# qcopter_lib_bb.net
KiCad netlist of a schematic drawn in EAGLE
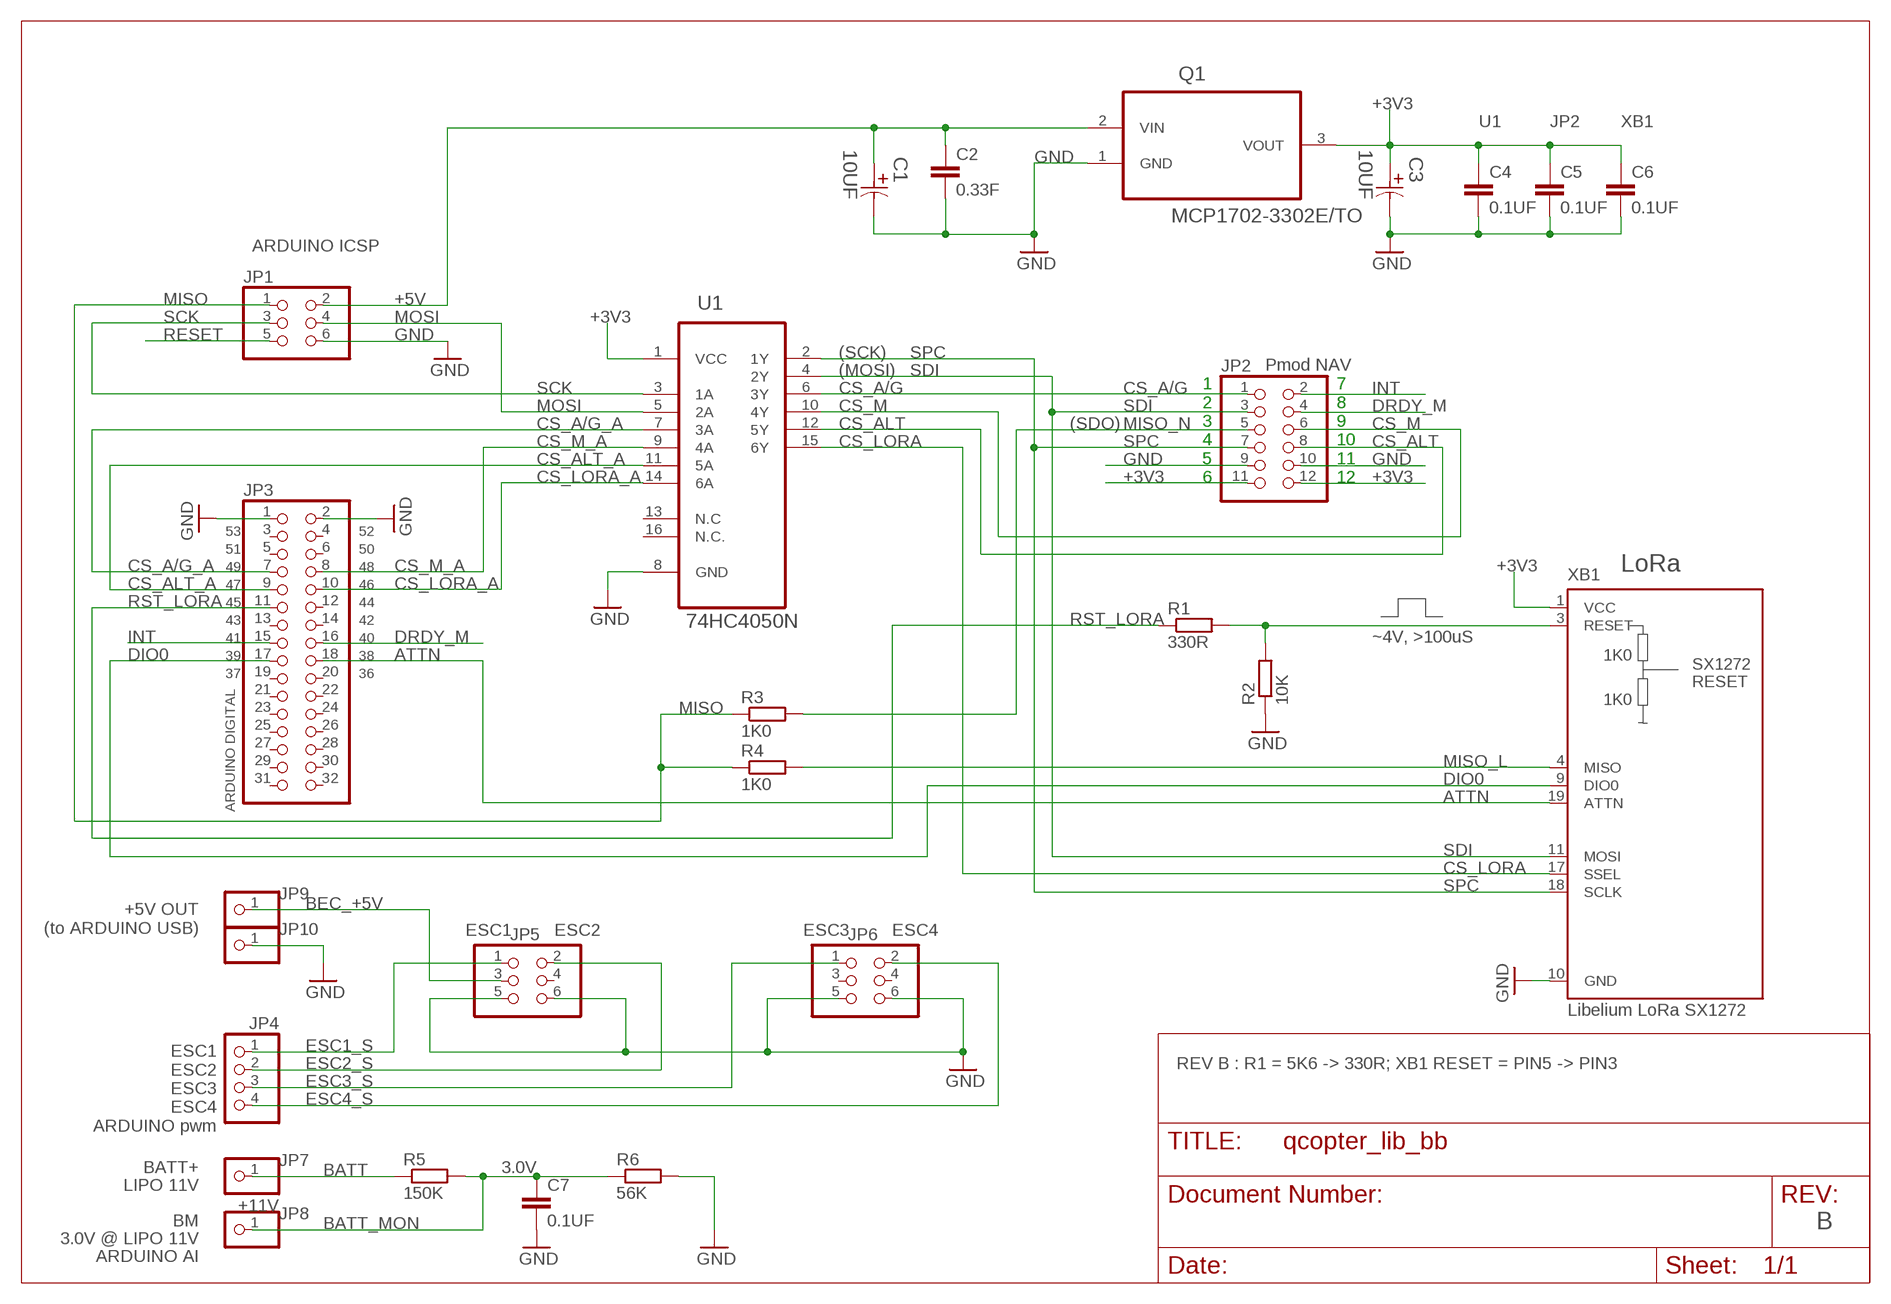
[diagram p0: schematic, sheet 1]

(export (version "E")
  (design (tool "Eeschema 10.0.6"))
  (components
    (comp (ref "C1")
      (value "10UF")
      (footprint "eagle-import:CAPPR200-500X1100")
      (fields (field (name "MPN") "ECA1EHG470") (field (name "TOLERANCE") "±20 %"))
      (libsource (lib "eagle-import") (part "ECA-D5XP21EHG470"))
    )
    (comp (ref "C2")
      (value "0.33F")
      (footprint "eagle-import:C5B2.5")
      (libsource (lib "eagle-import") (part "C5/2.5"))
    )
    (comp (ref "C3")
      (value "10UF")
      (footprint "eagle-import:CAPPR200-500X1100")
      (fields (field (name "MPN") "ECA1EHG470") (field (name "TOLERANCE") "±20 %"))
      (libsource (lib "eagle-import") (part "ECA-D5XP21EHG470"))
    )
    (comp (ref "C4")
      (value "0.1UF")
      (footprint "eagle-import:C5B2.5")
      (libsource (lib "eagle-import") (part "C5/2.5"))
    )
    (comp (ref "C5")
      (value "0.1UF")
      (footprint "eagle-import:C5B2.5")
      (libsource (lib "eagle-import") (part "C5/2.5"))
    )
    (comp (ref "C6")
      (value "0.1UF")
      (footprint "eagle-import:C5B2.5")
      (libsource (lib "eagle-import") (part "C5/2.5"))
    )
    (comp (ref "C7")
      (value "0.1UF")
      (footprint "eagle-import:C5B2.5")
      (libsource (lib "eagle-import") (part "C5/2.5"))
    )
    (comp (ref "JP1")
      (value "PINHD-2X3")
      (footprint "eagle-import:2X03")
      (libsource (lib "eagle-import") (part "PINHD-2X3"))
    )
    (comp (ref "JP2")
      (value "PINHD-2X6/90")
      (footprint "eagle-import:2X06_90")
      (libsource (lib "eagle-import") (part "PINHD-2X6/90"))
    )
    (comp (ref "JP3")
      (value "PINHD-2X16")
      (footprint "eagle-import:2X16")
      (libsource (lib "eagle-import") (part "PINHD-2X16"))
    )
    (comp (ref "JP4")
      (value "PINHD-1X4")
      (footprint "eagle-import:1X04")
      (libsource (lib "eagle-import") (part "PINHD-1X4"))
    )
    (comp (ref "JP5")
      (value "PINHD-2X3")
      (footprint "eagle-import:2X03")
      (libsource (lib "eagle-import") (part "PINHD-2X3"))
    )
    (comp (ref "JP6")
      (value "PINHD-2X3")
      (footprint "eagle-import:2X03")
      (libsource (lib "eagle-import") (part "PINHD-2X3"))
    )
    (comp (ref "JP7")
      (value "+11V")
      (footprint "eagle-import:1X01")
      (libsource (lib "eagle-import") (part "PINHD-1X1"))
    )
    (comp (ref "JP8")
      (value "PINHD-1X1")
      (footprint "eagle-import:1X01")
      (libsource (lib "eagle-import") (part "PINHD-1X1"))
    )
    (comp (ref "JP9")
      (value "PINHD-1X1")
      (footprint "eagle-import:1X01")
      (libsource (lib "eagle-import") (part "PINHD-1X1"))
    )
    (comp (ref "JP10")
      (value "PINHD-1X1")
      (footprint "eagle-import:1X01")
      (libsource (lib "eagle-import") (part "PINHD-1X1"))
    )
    (comp (ref "Q1")
      (value "MCP1702-3302E/TO")
      (footprint "eagle-import:TO127P254X533-3")
      (libsource (lib "eagle-import") (part "MCP1702-3302E/TO"))
    )
    (comp (ref "R1")
      (value "330R")
      (footprint "eagle-import:0207_10")
      (libsource (lib "eagle-import") (part "R-EU_0207/10"))
    )
    (comp (ref "R2")
      (value "10K")
      (footprint "eagle-import:0207_10")
      (libsource (lib "eagle-import") (part "R-EU_0207/10"))
    )
    (comp (ref "R3")
      (value "1K0")
      (footprint "eagle-import:0207_10")
      (libsource (lib "eagle-import") (part "R-EU_0207/10"))
    )
    (comp (ref "R4")
      (value "1K0")
      (footprint "eagle-import:0207_10")
      (libsource (lib "eagle-import") (part "R-EU_0207/10"))
    )
    (comp (ref "R5")
      (value "150K")
      (footprint "eagle-import:0207_10")
      (libsource (lib "eagle-import") (part "R-EU_0207/10"))
    )
    (comp (ref "R6")
      (value "56K")
      (footprint "eagle-import:0207_10")
      (libsource (lib "eagle-import") (part "R-EU_0207/10"))
    )
    (comp (ref "U1")
      (value "74HC4050N")
      (footprint "eagle-import:DIP254P762X420-16")
      (libsource (lib "eagle-import") (part "74HC4050N"))
    )
    (comp (ref "XB1")
      (value "Libelium LoRa SX1272")
      (footprint "eagle-import:XBEE")
      (libsource (lib "eagle-import") (part "SX1272-LORA"))
    )
  )
  (nets
    (net (code "1") (name "/+3V3") (class "Default")
      (node (ref "C3") (pin "1") (pinfunction "1_1") (pintype "passive"))
      (node (ref "C4") (pin "1") (pinfunction "1_1") (pintype "passive"))
      (node (ref "C5") (pin "1") (pinfunction "1_1") (pintype "passive"))
      (node (ref "C6") (pin "1") (pinfunction "1_1") (pintype "passive"))
      (node (ref "JP2") (pin "11") (pinfunction "11_11") (pintype "passive"))
      (node (ref "JP2") (pin "12") (pinfunction "12_12") (pintype "passive"))
      (node (ref "Q1") (pin "3") (pinfunction "VOUT_3") (pintype "output"))
      (node (ref "U1") (pin "1") (pinfunction "VCC_1") (pintype "power_in"))
      (node (ref "XB1") (pin "1") (pinfunction "VCC_1") (pintype "power_in"))
    )
    (net (code "2") (name "/+5V") (class "Default")
      (node (ref "C1") (pin "1") (pinfunction "1_1") (pintype "passive"))
      (node (ref "C2") (pin "1") (pinfunction "1_1") (pintype "passive"))
      (node (ref "JP1") (pin "2") (pinfunction "2_2") (pintype "passive"))
      (node (ref "Q1") (pin "2") (pinfunction "VIN_2") (pintype "input"))
    )
    (net (code "3") (name "/ATTN") (class "Default")
      (node (ref "JP3") (pin "18") (pinfunction "18_18") (pintype "passive"))
      (node (ref "XB1") (pin "19") (pinfunction "ATTN_19") (pintype "bidirectional"))
    )
    (net (code "4") (name "/BATT") (class "Default")
      (node (ref "JP7") (pin "1") (pinfunction "1_1") (pintype "passive"))
      (node (ref "R5") (pin "1") (pinfunction "1_1") (pintype "passive"))
    )
    (net (code "5") (name "/BATT_MON") (class "Default")
      (node (ref "C7") (pin "1") (pinfunction "1_1") (pintype "passive"))
      (node (ref "JP8") (pin "1") (pinfunction "1_1") (pintype "passive"))
      (node (ref "R5") (pin "2") (pinfunction "2_2") (pintype "passive"))
      (node (ref "R6") (pin "1") (pinfunction "1_1") (pintype "passive"))
    )
    (net (code "6") (name "/BEC_+5V") (class "Default")
      (node (ref "JP5") (pin "3") (pinfunction "3_3") (pintype "passive"))
      (node (ref "JP9") (pin "1") (pinfunction "1_1") (pintype "passive"))
    )
    (net (code "7") (name "/CS_ALT") (class "Default")
      (node (ref "JP2") (pin "8") (pinfunction "8_8") (pintype "passive"))
      (node (ref "U1") (pin "12") (pinfunction "5Y_12") (pintype "output"))
    )
    (net (code "8") (name "/CS_ALT_A") (class "Default")
      (node (ref "JP3") (pin "9") (pinfunction "9_9") (pintype "passive"))
      (node (ref "U1") (pin "11") (pinfunction "5A_11") (pintype "input"))
    )
    (net (code "9") (name "/CS_A{slash}G") (class "Default")
      (node (ref "JP2") (pin "1") (pinfunction "1_1") (pintype "passive"))
      (node (ref "U1") (pin "6") (pinfunction "3Y_6") (pintype "output"))
    )
    (net (code "10") (name "/CS_A{slash}G_A") (class "Default")
      (node (ref "JP3") (pin "7") (pinfunction "7_7") (pintype "passive"))
      (node (ref "U1") (pin "7") (pinfunction "3A_7") (pintype "input"))
    )
    (net (code "11") (name "/CS_LORA") (class "Default")
      (node (ref "U1") (pin "15") (pinfunction "6Y_15") (pintype "output"))
      (node (ref "XB1") (pin "17") (pinfunction "SSEL_17") (pintype "input"))
    )
    (net (code "12") (name "/CS_LORA_A") (class "Default")
      (node (ref "JP3") (pin "10") (pinfunction "10_10") (pintype "passive"))
      (node (ref "U1") (pin "14") (pinfunction "6A_14") (pintype "input"))
    )
    (net (code "13") (name "/CS_M") (class "Default")
      (node (ref "JP2") (pin "6") (pinfunction "6_6") (pintype "passive"))
      (node (ref "U1") (pin "10") (pinfunction "4Y_10") (pintype "output"))
    )
    (net (code "14") (name "/CS_M_A") (class "Default")
      (node (ref "JP3") (pin "8") (pinfunction "8_8") (pintype "passive"))
      (node (ref "U1") (pin "9") (pinfunction "4A_9") (pintype "input"))
    )
    (net (code "15") (name "/DIO0") (class "Default")
      (node (ref "JP3") (pin "17") (pinfunction "17_17") (pintype "passive"))
      (node (ref "XB1") (pin "9") (pinfunction "DIO0_9") (pintype "bidirectional"))
    )
    (net (code "16") (name "/DRDY_M") (class "Default")
      (node (ref "JP2") (pin "4") (pinfunction "4_4") (pintype "passive"))
      (node (ref "JP3") (pin "16") (pinfunction "16_16") (pintype "passive"))
    )
    (net (code "17") (name "/ESC1_S") (class "Default")
      (node (ref "JP4") (pin "1") (pinfunction "1_1") (pintype "passive"))
      (node (ref "JP5") (pin "1") (pinfunction "1_1") (pintype "passive"))
    )
    (net (code "18") (name "/ESC2_S") (class "Default")
      (node (ref "JP4") (pin "2") (pinfunction "2_2") (pintype "passive"))
      (node (ref "JP5") (pin "2") (pinfunction "2_2") (pintype "passive"))
    )
    (net (code "19") (name "/ESC3_S") (class "Default")
      (node (ref "JP4") (pin "3") (pinfunction "3_3") (pintype "passive"))
      (node (ref "JP6") (pin "1") (pinfunction "1_1") (pintype "passive"))
    )
    (net (code "20") (name "/ESC4_S") (class "Default")
      (node (ref "JP4") (pin "4") (pinfunction "4_4") (pintype "passive"))
      (node (ref "JP6") (pin "2") (pinfunction "2_2") (pintype "passive"))
    )
    (net (code "21") (name "/INT") (class "Default")
      (node (ref "JP2") (pin "2") (pinfunction "2_2") (pintype "passive"))
      (node (ref "JP3") (pin "15") (pinfunction "15_15") (pintype "passive"))
    )
    (net (code "22") (name "/MISO") (class "Default")
      (node (ref "JP1") (pin "1") (pinfunction "1_1") (pintype "passive"))
      (node (ref "R3") (pin "1") (pinfunction "1_1") (pintype "passive"))
      (node (ref "R4") (pin "1") (pinfunction "1_1") (pintype "passive"))
    )
    (net (code "23") (name "/MISO_L") (class "Default")
      (node (ref "R4") (pin "2") (pinfunction "2_2") (pintype "passive"))
      (node (ref "XB1") (pin "4") (pinfunction "MISO_4") (pintype "output"))
    )
    (net (code "24") (name "/MISO_N") (class "Default")
      (node (ref "JP2") (pin "5") (pinfunction "5_5") (pintype "passive"))
      (node (ref "R3") (pin "2") (pinfunction "2_2") (pintype "passive"))
    )
    (net (code "25") (name "/MOSI") (class "Default")
      (node (ref "JP1") (pin "4") (pinfunction "4_4") (pintype "passive"))
      (node (ref "U1") (pin "5") (pinfunction "2A_5") (pintype "input"))
    )
    (net (code "26") (name "/RESET") (class "Default")
      (node (ref "JP1") (pin "5") (pinfunction "5_5") (pintype "passive"))
    )
    (net (code "27") (name "/RST_LORA") (class "Default")
      (node (ref "JP3") (pin "11") (pinfunction "11_11") (pintype "passive"))
      (node (ref "R1") (pin "1") (pinfunction "1_1") (pintype "passive"))
    )
    (net (code "28") (name "/SCK") (class "Default")
      (node (ref "JP1") (pin "3") (pinfunction "3_3") (pintype "passive"))
      (node (ref "U1") (pin "3") (pinfunction "1A_3") (pintype "input"))
    )
    (net (code "29") (name "/SDI") (class "Default")
      (node (ref "JP2") (pin "3") (pinfunction "3_3") (pintype "passive"))
      (node (ref "U1") (pin "4") (pinfunction "2Y_4") (pintype "output"))
      (node (ref "XB1") (pin "11") (pinfunction "MOSI_11") (pintype "input"))
    )
    (net (code "30") (name "/SPC") (class "Default")
      (node (ref "JP2") (pin "7") (pinfunction "7_7") (pintype "passive"))
      (node (ref "U1") (pin "2") (pinfunction "1Y_2") (pintype "output"))
      (node (ref "XB1") (pin "18") (pinfunction "SCLK_18") (pintype "input"))
    )
    (net (code "31") (name "GND") (class "Default")
      (node (ref "C1") (pin "2") (pinfunction "2_2") (pintype "passive"))
      (node (ref "C2") (pin "2") (pinfunction "2_2") (pintype "passive"))
      (node (ref "C3") (pin "2") (pinfunction "2_2") (pintype "passive"))
      (node (ref "C4") (pin "2") (pinfunction "2_2") (pintype "passive"))
      (node (ref "C5") (pin "2") (pinfunction "2_2") (pintype "passive"))
      (node (ref "C6") (pin "2") (pinfunction "2_2") (pintype "passive"))
      (node (ref "C7") (pin "2") (pinfunction "2_2") (pintype "passive"))
      (node (ref "JP1") (pin "6") (pinfunction "6_6") (pintype "passive"))
      (node (ref "JP10") (pin "1") (pinfunction "1_1") (pintype "passive"))
      (node (ref "JP2") (pin "10") (pinfunction "10_10") (pintype "passive"))
      (node (ref "JP2") (pin "9") (pinfunction "9_9") (pintype "passive"))
      (node (ref "JP3") (pin "1") (pinfunction "1_1") (pintype "passive"))
      (node (ref "JP3") (pin "2") (pinfunction "2_2") (pintype "passive"))
      (node (ref "JP5") (pin "5") (pinfunction "5_5") (pintype "passive"))
      (node (ref "JP5") (pin "6") (pinfunction "6_6") (pintype "passive"))
      (node (ref "JP6") (pin "5") (pinfunction "5_5") (pintype "passive"))
      (node (ref "JP6") (pin "6") (pinfunction "6_6") (pintype "passive"))
      (node (ref "Q1") (pin "1") (pinfunction "GND_1") (pintype "passive"))
      (node (ref "R2") (pin "1") (pinfunction "1_1") (pintype "passive"))
      (node (ref "R6") (pin "2") (pinfunction "2_2") (pintype "passive"))
      (node (ref "U1") (pin "8") (pinfunction "GND_8") (pintype "passive"))
      (node (ref "XB1") (pin "10") (pinfunction "GND_10") (pintype "power_in"))
    )
    (net (code "32") (name "Net-(XB1-RESET)") (class "Default")
      (node (ref "R1") (pin "2") (pinfunction "2_2") (pintype "passive"))
      (node (ref "R2") (pin "2") (pinfunction "2_2") (pintype "passive"))
      (node (ref "XB1") (pin "3") (pinfunction "RESET_3") (pintype "input"))
    )
    (net (code "33") (name "unconnected-(JP3-Pad3)") (class "Default")
      (node (ref "JP3") (pin "3") (pinfunction "3_3") (pintype "passive"))
    )
    (net (code "34") (name "unconnected-(JP3-Pad4)") (class "Default")
      (node (ref "JP3") (pin "4") (pinfunction "4_4") (pintype "passive"))
    )
    (net (code "35") (name "unconnected-(JP3-Pad5)") (class "Default")
      (node (ref "JP3") (pin "5") (pinfunction "5_5") (pintype "passive"))
    )
    (net (code "36") (name "unconnected-(JP3-Pad6)") (class "Default")
      (node (ref "JP3") (pin "6") (pinfunction "6_6") (pintype "passive"))
    )
    (net (code "37") (name "unconnected-(JP3-Pad12)") (class "Default")
      (node (ref "JP3") (pin "12") (pinfunction "12_12") (pintype "passive"))
    )
    (net (code "38") (name "unconnected-(JP3-Pad13)") (class "Default")
      (node (ref "JP3") (pin "13") (pinfunction "13_13") (pintype "passive"))
    )
    (net (code "39") (name "unconnected-(JP3-Pad14)") (class "Default")
      (node (ref "JP3") (pin "14") (pinfunction "14_14") (pintype "passive"))
    )
    (net (code "40") (name "unconnected-(JP3-Pad19)") (class "Default")
      (node (ref "JP3") (pin "19") (pinfunction "19_19") (pintype "passive"))
    )
    (net (code "41") (name "unconnected-(JP3-Pad20)") (class "Default")
      (node (ref "JP3") (pin "20") (pinfunction "20_20") (pintype "passive"))
    )
    (net (code "42") (name "unconnected-(JP3-Pad21)") (class "Default")
      (node (ref "JP3") (pin "21") (pinfunction "21_21") (pintype "passive"))
    )
    (net (code "43") (name "unconnected-(JP3-Pad22)") (class "Default")
      (node (ref "JP3") (pin "22") (pinfunction "22_22") (pintype "passive"))
    )
    (net (code "44") (name "unconnected-(JP3-Pad23)") (class "Default")
      (node (ref "JP3") (pin "23") (pinfunction "23_23") (pintype "passive"))
    )
    (net (code "45") (name "unconnected-(JP3-Pad24)") (class "Default")
      (node (ref "JP3") (pin "24") (pinfunction "24_24") (pintype "passive"))
    )
    (net (code "46") (name "unconnected-(JP3-Pad25)") (class "Default")
      (node (ref "JP3") (pin "25") (pinfunction "25_25") (pintype "passive"))
    )
    (net (code "47") (name "unconnected-(JP3-Pad26)") (class "Default")
      (node (ref "JP3") (pin "26") (pinfunction "26_26") (pintype "passive"))
    )
    (net (code "48") (name "unconnected-(JP3-Pad27)") (class "Default")
      (node (ref "JP3") (pin "27") (pinfunction "27_27") (pintype "passive"))
    )
    (net (code "49") (name "unconnected-(JP3-Pad28)") (class "Default")
      (node (ref "JP3") (pin "28") (pinfunction "28_28") (pintype "passive"))
    )
    (net (code "50") (name "unconnected-(JP3-Pad29)") (class "Default")
      (node (ref "JP3") (pin "29") (pinfunction "29_29") (pintype "passive"))
    )
    (net (code "51") (name "unconnected-(JP3-Pad30)") (class "Default")
      (node (ref "JP3") (pin "30") (pinfunction "30_30") (pintype "passive"))
    )
    (net (code "52") (name "unconnected-(JP3-Pad31)") (class "Default")
      (node (ref "JP3") (pin "31") (pinfunction "31_31") (pintype "passive"))
    )
    (net (code "53") (name "unconnected-(JP3-Pad32)") (class "Default")
      (node (ref "JP3") (pin "32") (pinfunction "32_32") (pintype "passive"))
    )
    (net (code "54") (name "unconnected-(JP5-Pad4)") (class "Default")
      (node (ref "JP5") (pin "4") (pinfunction "4_4") (pintype "passive"))
    )
    (net (code "55") (name "unconnected-(JP6-Pad3)") (class "Default")
      (node (ref "JP6") (pin "3") (pinfunction "3_3") (pintype "passive"))
    )
    (net (code "56") (name "unconnected-(JP6-Pad4)") (class "Default")
      (node (ref "JP6") (pin "4") (pinfunction "4_4") (pintype "passive"))
    )
    (net (code "57") (name "unconnected-(U1-N.C-Pad13)") (class "Default")
      (node (ref "U1") (pin "13") (pinfunction "N.C_13") (pintype "no_connect"))
    )
    (net (code "58") (name "unconnected-(U1-N.C.-Pad16)") (class "Default")
      (node (ref "U1") (pin "16") (pinfunction "N.C._16") (pintype "no_connect"))
    )
  )
)
